# 4_PowerManagement.net
KiCad netlist of a schematic drawn in Altium Designer
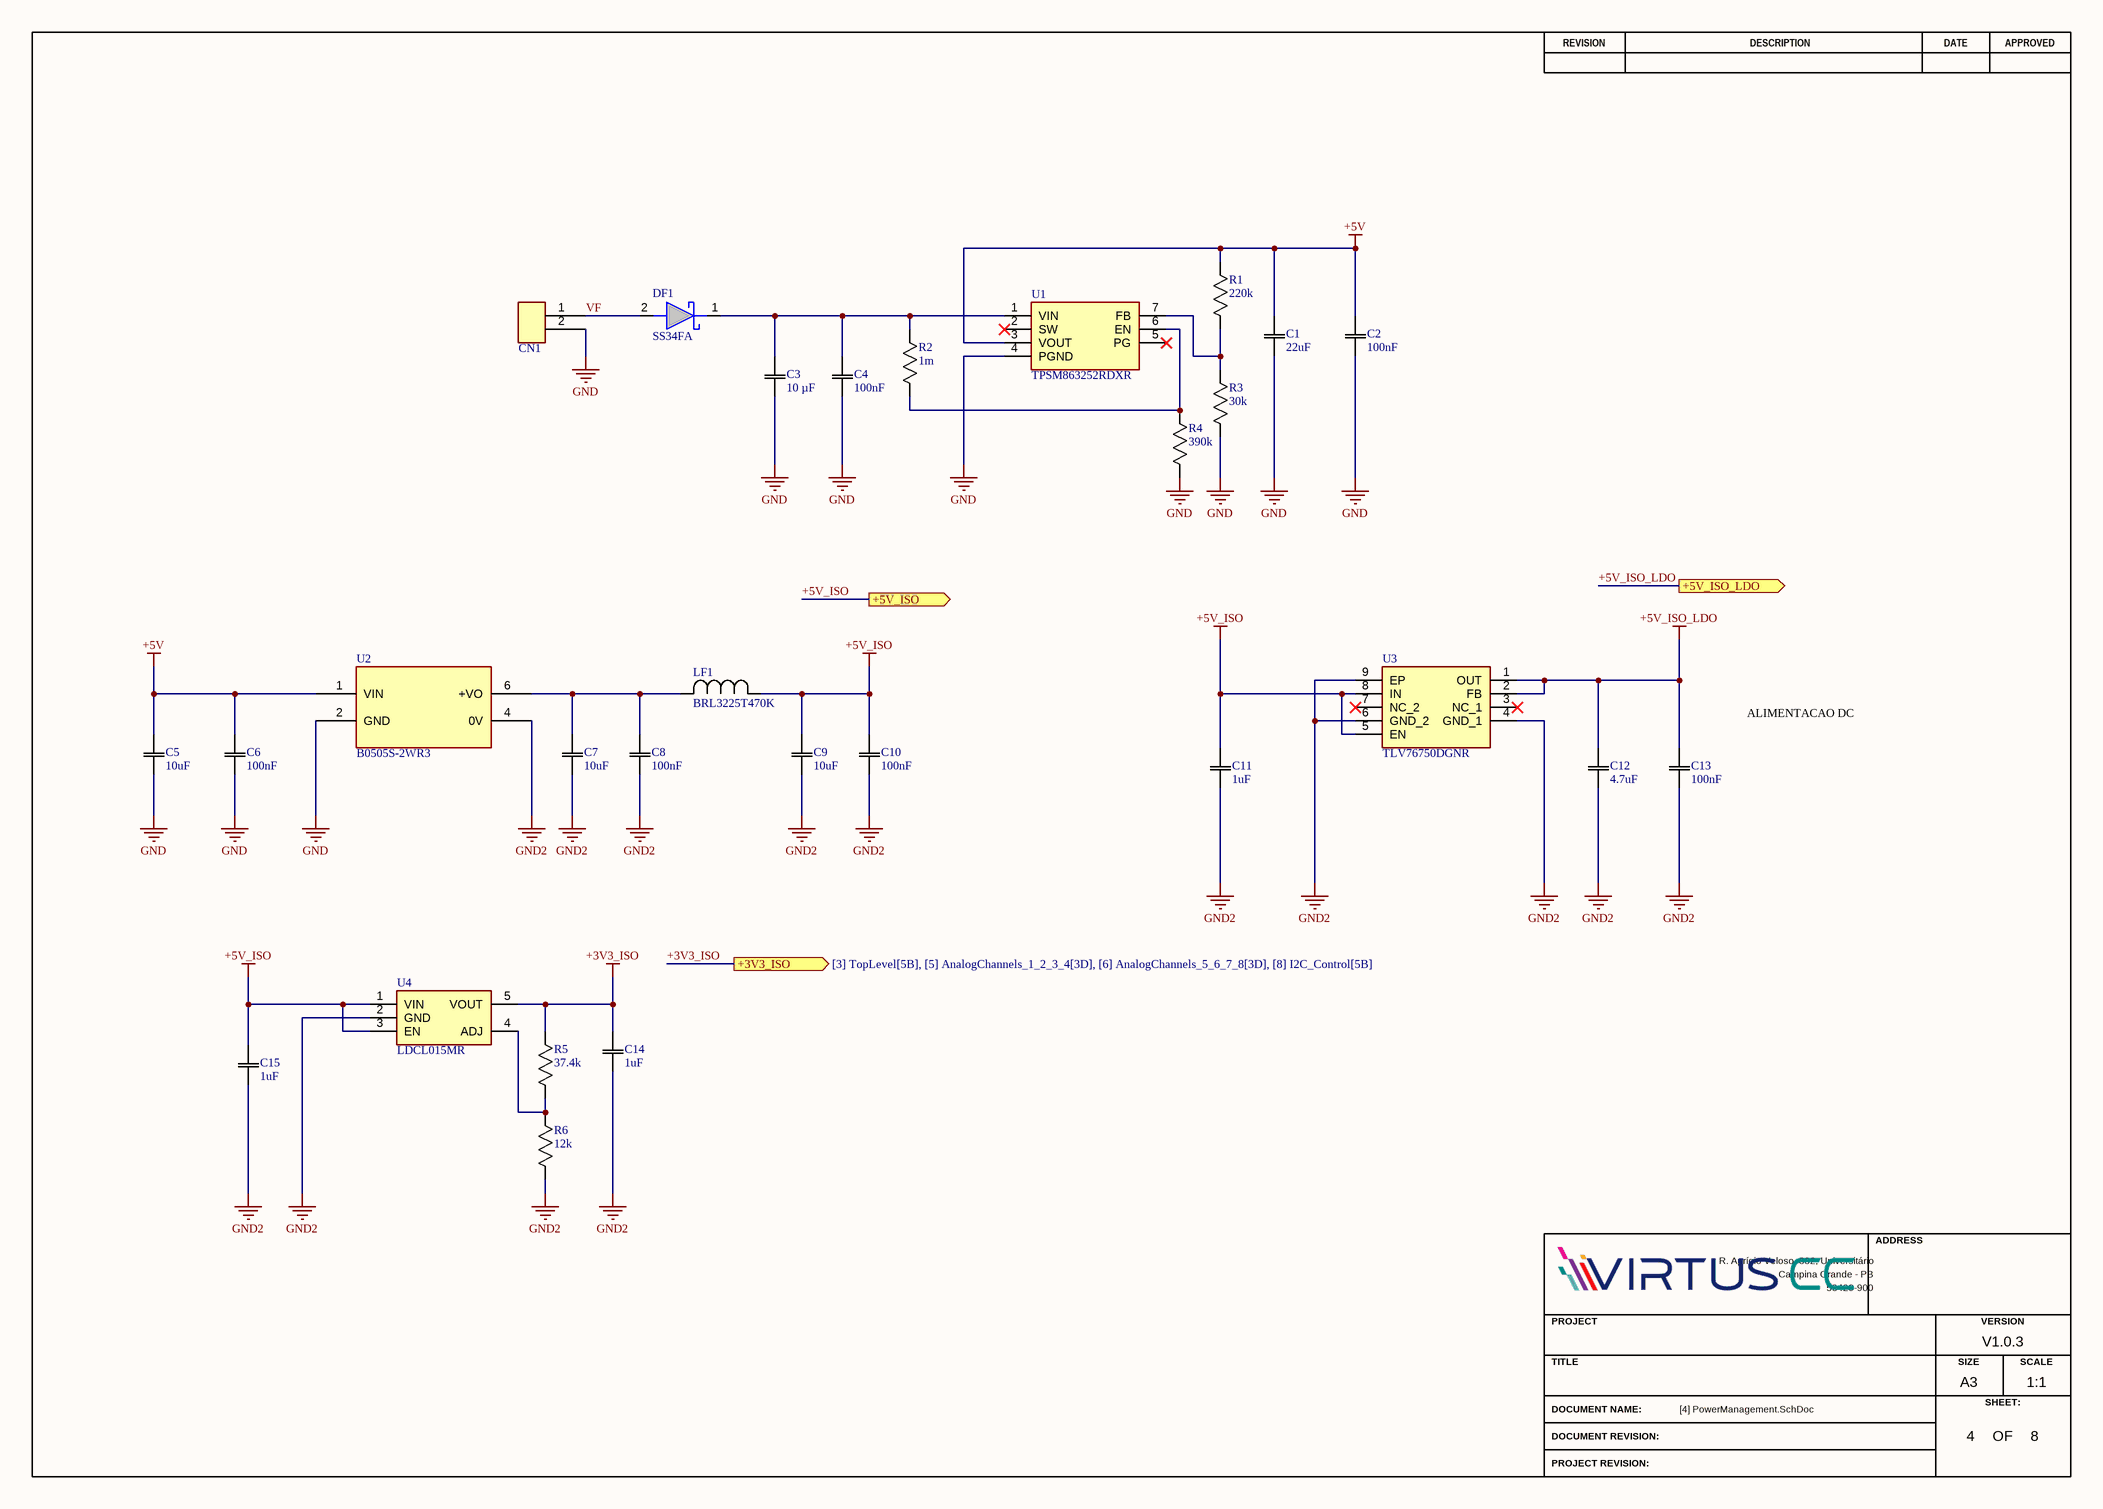
[diagram p0: [4] PowerManagement.SchDoc]

(export (version "E")
  (design (tool "Eeschema 10.0.6"))
  (components
    (comp (ref "C1")
      (value "22uF")
      (footprint "CAPC1608X06N")
      (description "22 µF ±20% 16V Ceramic Capacitor X5R 0603 (1608 Metric)")
      (fields
        (field (name "MANUFACTURER_PART_NUMBER") "CL10A226MO7JZNC")
        (field (name "COPYRIGHT") "Copyright (C) 2026 Ultra Librarian. All rights reserved.")
      )
      (libsource (lib "PCEIOT") (part "CL10A226MO7JZNC"))
    )
    (comp (ref "C2")
      (value "100nF")
      (footprint "CAPC1005X40N")
      (description "0.1 µF ±10% 50V Ceramic Capacitor X7R 0402 (1005 Metric)")
      (fields
        (field (name "MANUFACTURER_PART_NUMBER") "GCM155R71H104KE02D")
        (field (name "COPYRIGHT") "Copyright (C) 2026 Ultra Librarian. All rights reserved.")
      )
      (libsource (lib "PCEIOT") (part "GCM155R71H104KE02D"))
    )
    (comp (ref "C3")
      (value "10 µF")
      (footprint "CAPC1608X06N")
      (description "10 µF ±20% 25V Ceramic Capacitor X5R 0603 (1608 Metric)")
      (fields
        (field (name "MANUFACTURER_PART_NUMBER") "CL10A106MA8NRNC")
        (field (name "COPYRIGHT") "Copyright (C) 2025 Ultra Librarian. All rights reserved.")
      )
      (libsource (lib "PCEIOT") (part "CL10A106MA8NRNC"))
    )
    (comp (ref "C4")
      (value "100nF")
      (footprint "CAPC1005X40N")
      (description "0.1 µF ±10% 50V Ceramic Capacitor X7R 0402 (1005 Metric)")
      (fields
        (field (name "MANUFACTURER_PART_NUMBER") "GCM155R71H104KE02D")
        (field (name "COPYRIGHT") "Copyright (C) 2026 Ultra Librarian. All rights reserved.")
      )
      (libsource (lib "PCEIOT") (part "GCM155R71H104KE02D"))
    )
    (comp (ref "C5")
      (value "10uF")
      (footprint "CAPC1005X40N")
      (description "10 µF ±20% 10V Ceramic Capacitor X5R 0402 (1005 Metric)")
      (fields
        (field (name "MANUFACTURER_PART_NUMBER") "GRT155R61A106ME13D")
        (field (name "COPYRIGHT") "Copyright (C) 2026 Ultra Librarian. All rights reserved.")
      )
      (libsource (lib "PCEIOT") (part "GRT155R61A106ME13D"))
    )
    (comp (ref "C6")
      (value "100nF")
      (footprint "CAPC1005X40N")
      (description "0.1 µF ±10% 50V Ceramic Capacitor X7R 0402 (1005 Metric)")
      (fields
        (field (name "MANUFACTURER_PART_NUMBER") "GCM155R71H104KE02D")
        (field (name "COPYRIGHT") "Copyright (C) 2026 Ultra Librarian. All rights reserved.")
      )
      (libsource (lib "PCEIOT") (part "GCM155R71H104KE02D"))
    )
    (comp (ref "C7")
      (value "10uF")
      (footprint "CAPC1005X40N")
      (description "10 µF ±20% 10V Ceramic Capacitor X5R 0402 (1005 Metric)")
      (fields
        (field (name "MANUFACTURER_PART_NUMBER") "GRT155R61A106ME13D")
        (field (name "COPYRIGHT") "Copyright (C) 2026 Ultra Librarian. All rights reserved.")
      )
      (libsource (lib "PCEIOT") (part "GRT155R61A106ME13D"))
    )
    (comp (ref "C8")
      (value "100nF")
      (footprint "CAPC1005X40N")
      (description "0.1 µF ±10% 50V Ceramic Capacitor X7R 0402 (1005 Metric)")
      (fields
        (field (name "MANUFACTURER_PART_NUMBER") "GCM155R71H104KE02D")
        (field (name "COPYRIGHT") "Copyright (C) 2026 Ultra Librarian. All rights reserved.")
      )
      (libsource (lib "PCEIOT") (part "GCM155R71H104KE02D"))
    )
    (comp (ref "C9")
      (value "10uF")
      (footprint "CAPC1005X40N")
      (description "10 µF ±20% 10V Ceramic Capacitor X5R 0402 (1005 Metric)")
      (fields
        (field (name "MANUFACTURER_PART_NUMBER") "GRT155R61A106ME13D")
        (field (name "COPYRIGHT") "Copyright (C) 2026 Ultra Librarian. All rights reserved.")
      )
      (libsource (lib "PCEIOT") (part "GRT155R61A106ME13D"))
    )
    (comp (ref "C10")
      (value "100nF")
      (footprint "CAPC1005X40N")
      (description "0.1 µF ±10% 50V Ceramic Capacitor X7R 0402 (1005 Metric)")
      (fields
        (field (name "MANUFACTURER_PART_NUMBER") "GCM155R71H104KE02D")
        (field (name "COPYRIGHT") "Copyright (C) 2026 Ultra Librarian. All rights reserved.")
      )
      (libsource (lib "PCEIOT") (part "GCM155R71H104KE02D"))
    )
    (comp (ref "C11")
      (value "1uF")
      (footprint "CAPC1005X40N")
      (description "1 µF ±10% 10V Ceramic Capacitor X7R 0402 (1005 Metric)")
      (fields
        (field (name "MANUFACTURER_PART_NUMBER") "GRM155Z71A105KE01D")
        (field (name "COPYRIGHT") "Copyright (C) 2025 Ultra Librarian. All rights reserved.")
      )
      (libsource (lib "PCEIOT") (part "GRM155Z71A105KE01D"))
    )
    (comp (ref "C12")
      (value "4.7uF")
      (footprint "CAPC1005X40N")
      (description "4.7 µF ±20% 10V Ceramic Capacitor X5R 0402 (1005 Metric)")
      (fields
        (field (name "MANUFACTURER_PART_NUMBER") "GRM155R61A475MEAAD")
        (field (name "COPYRIGHT") "Copyright (C) 2025 Ultra Librarian. All rights reserved.")
      )
      (libsource (lib "PCEIOT") (part "GRM155R61A475MEAAD"))
    )
    (comp (ref "C13")
      (value "100nF")
      (footprint "CAPC1005X40N")
      (description "0.1 µF ±10% 50V Ceramic Capacitor X7R 0402 (1005 Metric)")
      (fields
        (field (name "MANUFACTURER_PART_NUMBER") "GCM155R71H104KE02D")
        (field (name "COPYRIGHT") "Copyright (C) 2026 Ultra Librarian. All rights reserved.")
      )
      (libsource (lib "PCEIOT") (part "GCM155R71H104KE02D"))
    )
    (comp (ref "C14")
      (value "1uF")
      (footprint "CAPC1005X40N")
      (description "1 µF ±10% 10V Ceramic Capacitor X7R 0402 (1005 Metric)")
      (fields
        (field (name "MANUFACTURER_PART_NUMBER") "GRM155Z71A105KE01D")
        (field (name "COPYRIGHT") "Copyright (C) 2025 Ultra Librarian. All rights reserved.")
      )
      (libsource (lib "PCEIOT") (part "GRM155Z71A105KE01D"))
    )
    (comp (ref "C15")
      (value "1uF")
      (footprint "CAPC1005X40N")
      (description "1 µF ±10% 10V Ceramic Capacitor X7R 0402 (1005 Metric)")
      (fields
        (field (name "MANUFACTURER_PART_NUMBER") "GRM155Z71A105KE01D")
        (field (name "COPYRIGHT") "Copyright (C) 2025 Ultra Librarian. All rights reserved.")
      )
      (libsource (lib "PCEIOT") (part "GRM155Z71A105KE01D"))
    )
    (comp (ref "CN1")
      (value "JDCN2.0")
      (footprint "JACK - P4")
      (description "Conector Fonte. JDCN2.0")
      (libsource (lib "PCEIOT") (part "JDCN2.0"))
    )
    (comp (ref "DF1")
      (value "SS34FA")
      (footprint "SODFL3618X143N")
      (fields (field (name "MOUSER PART NUMBER") "512-SS34FA"))
      (libsource (lib "PCEIOT") (part "SS34FA"))
    )
    (comp (ref "LF1")
      (value "BRL3225T470K")
      (footprint "IND_TAIYO_BRL3225_TAY")
      (description "47 µH Semi-Shielded Drum Core, Wirewound Inductor 390 mA 1.2Ohm Max 1210 (3225 Metric)")
      (fields (field (name "COPYRIGHT") "Copyright (C) 2025 Ultra Librarian. All rights reserved."))
      (libsource (lib "PCEIOT") (part "BRL3225T470K"))
    )
    (comp (ref "R1")
      (value "220k")
      (footprint "RESC1005X40N")
      (description "220 kOhms ±1% 0.063W, 1/16W Chip Resistor 0402 (1005 Metric) Moisture Resistant Thick Film")
      (fields
        (field (name "MANUFACTURER_PART_NUMBER") "RC0402FR-07220KL")
        (field (name "COPYRIGHT") "Copyright (C) 2026 Ultra Librarian. All rights reserved.")
      )
      (libsource (lib "PCEIOT") (part "RC0402FR-07220KL"))
    )
    (comp (ref "R2")
      (value "1m")
      (footprint "RESC1005X40N")
      (description "1 MOhms ±1% 0.063W, 1/16W Chip Resistor 0402 (1005 Metric) Moisture Resistant Thick Film")
      (fields
        (field (name "MANUFACTURER_PART_NUMBER") "RC0402FR-071ML")
        (field (name "COPYRIGHT") "Copyright (C) 2026 Ultra Librarian. All rights reserved.")
      )
      (libsource (lib "PCEIOT") (part "RC0402FR-071ML"))
    )
    (comp (ref "R3")
      (value "30k")
      (footprint "RESC1005X40N")
      (description "30 kOhms ±1% 0.063W, 1/16W Chip Resistor 0402 (1005 Metric) Moisture Resistant Thick Film")
      (fields
        (field (name "MANUFACTURER_PART_NUMBER") "RC0402FR-0730KL")
        (field (name "COPYRIGHT") "Copyright (C) 2026 Ultra Librarian. All rights reserved.")
      )
      (libsource (lib "PCEIOT") (part "RC0402FR-0730KL"))
    )
    (comp (ref "R4")
      (value "390k")
      (footprint "RESC1005X40N")
      (description "390 kOhms ±1% 0.063W, 1/16W Chip Resistor 0402 (1005 Metric) Moisture Resistant Thick Film")
      (fields
        (field (name "MANUFACTURER_PART_NUMBER") "RC0402FR-07390KL")
        (field (name "COPYRIGHT") "Copyright (C) 2026 Ultra Librarian. All rights reserved.")
      )
      (libsource (lib "PCEIOT") (part "RC0402FR-07390KL"))
    )
    (comp (ref "R5")
      (value "37.4k")
      (footprint "RESC1005X40N")
      (description "37.4 kOhms ±1% 0.063W, 1/16W Chip Resistor 0402 (1005 Metric) Moisture Resistant Thick Film")
      (fields
        (field (name "MANUFACTURER_PART_NUMBER") "RC0402FR-0737K4L")
        (field (name "COPYRIGHT") "Copyright (C) 2026 Ultra Librarian. All rights reserved.")
      )
      (libsource (lib "PCEIOT") (part "RC0402FR-0737K4L"))
    )
    (comp (ref "R6")
      (value "12k")
      (footprint "RESC1005X40N")
      (description "12 kOhms ±1% 0.063W, 1/16W Chip Resistor 0402 (1005 Metric) Moisture Resistant Thick Film")
      (fields
        (field (name "MANUFACTURER_PART_NUMBER") "RC0402FR-0712KL")
        (field (name "COPYRIGHT") "Copyright (C) 2025 Ultra Librarian. All rights reserved.")
      )
      (libsource (lib "PCEIOT") (part "RC0402FR-0712KL"))
    )
    (comp (ref "U1")
      (value "TPSM863252RDXR")
      (footprint "RDX0007A-MFG - 2")
      (description "3-V to 17-V input voltage, 3-A Eco-mode synchronous buck module 7-QFN-FCMOD -40 to 125")
      (fields (field (name "COPYRIGHT") "Copyright (C) 2025 Ultra Librarian. All rights reserved."))
      (libsource (lib "PCEIOT") (part "TPSM863252RDXR"))
    )
    (comp (ref "U2")
      (value "B0505S-2WR3")
      (footprint "B_S-2WR2_MNS")
      (description "Isolated Module DC DC Converter 1 Output 5V 400mA 4.5V - 5.5V Input")
      (fields (field (name "COPYRIGHT") "Copyright (C) 2026 Ultra Librarian. All rights reserved."))
      (libsource (lib "PCEIOT") (part "B0505S-2WR3"))
    )
    (comp (ref "U3")
      (value "TLV76750DGNR")
      (footprint "VSSOP_0DGNR_TEX")
      (fields (field (name "MOUSER PART NUMBER") "595-TLV76750DGNR"))
      (libsource (lib "PCEIOT") (part "TLV76750DGNR"))
    )
    (comp (ref "U4")
      (value "LDCL015MR")
      (footprint "SOT95P280X145-5N")
      (description "Linear Voltage Regulator IC Positive Adjustable 1 Output 150mA SOT-23-5")
      (fields (field (name "MOUSER PART NUMBER") "511-LDCL015MR"))
      (libsource (lib "PCEIOT") (part "LDCL015MR"))
    )
  )
  (nets
    (net (code "1") (name "+3V3_ISO") (class "Default")
      (node (ref "C14") (pin "2") (pinfunction "2_2") (pintype "passive"))
      (node (ref "R5") (pin "1") (pinfunction "1_1") (pintype "passive"))
      (node (ref "U4") (pin "5") (pinfunction "VOUT_5") (pintype "passive"))
    )
    (net (code "2") (name "+5V") (class "Default")
      (node (ref "C1") (pin "2") (pinfunction "2_2") (pintype "passive"))
      (node (ref "C2") (pin "2") (pinfunction "2_2") (pintype "passive"))
      (node (ref "C5") (pin "2") (pinfunction "2_2") (pintype "passive"))
      (node (ref "C6") (pin "2") (pinfunction "2_2") (pintype "passive"))
      (node (ref "R1") (pin "1") (pinfunction "1_1") (pintype "passive"))
      (node (ref "U1") (pin "3") (pinfunction "VOUT_3") (pintype "power_in"))
      (node (ref "U2") (pin "1") (pinfunction "VIN_1") (pintype "power_in"))
    )
    (net (code "3") (name "+5V_ISO") (class "Default")
      (node (ref "C10") (pin "2") (pinfunction "2_2") (pintype "passive"))
      (node (ref "C11") (pin "2") (pinfunction "2_2") (pintype "passive"))
      (node (ref "C15") (pin "2") (pinfunction "2_2") (pintype "passive"))
      (node (ref "C9") (pin "2") (pinfunction "2_2") (pintype "passive"))
      (node (ref "LF1") (pin "1") (pinfunction "1_1") (pintype "passive"))
      (node (ref "U3") (pin "5") (pinfunction "EN_5") (pintype "passive"))
      (node (ref "U3") (pin "8") (pinfunction "IN_8") (pintype "passive"))
      (node (ref "U4") (pin "1") (pinfunction "VIN_1") (pintype "passive"))
      (node (ref "U4") (pin "3") (pinfunction "EN_3") (pintype "passive"))
    )
    (net (code "4") (name "+5V_ISO_LDO") (class "Default")
      (node (ref "C12") (pin "2") (pinfunction "2_2") (pintype "passive"))
      (node (ref "C13") (pin "2") (pinfunction "2_2") (pintype "passive"))
      (node (ref "U3") (pin "1") (pinfunction "OUT_1") (pintype "passive"))
      (node (ref "U3") (pin "2") (pinfunction "FB_2") (pintype "passive"))
    )
    (net (code "5") (name "/VF") (class "Default")
      (node (ref "CN1") (pin "1") (pinfunction "1_1") (pintype "passive"))
      (node (ref "DF1") (pin "2") (pinfunction "A_2") (pintype "passive"))
    )
    (net (code "6") (name "GND") (class "Default")
      (node (ref "C1") (pin "1") (pinfunction "1_1") (pintype "passive"))
      (node (ref "C2") (pin "1") (pinfunction "1_1") (pintype "passive"))
      (node (ref "C3") (pin "1") (pinfunction "1_1") (pintype "passive"))
      (node (ref "C4") (pin "1") (pinfunction "1_1") (pintype "passive"))
      (node (ref "C5") (pin "1") (pinfunction "1_1") (pintype "passive"))
      (node (ref "C6") (pin "1") (pinfunction "1_1") (pintype "passive"))
      (node (ref "CN1") (pin "2") (pinfunction "2_2") (pintype "passive"))
      (node (ref "R3") (pin "2") (pinfunction "2_2") (pintype "passive"))
      (node (ref "R4") (pin "2") (pinfunction "2_2") (pintype "passive"))
      (node (ref "U1") (pin "4") (pinfunction "PGND_4") (pintype "power_in"))
      (node (ref "U2") (pin "2") (pinfunction "GND_2") (pintype "power_in"))
    )
    (net (code "7") (name "GND2") (class "Default")
      (node (ref "C10") (pin "1") (pinfunction "1_1") (pintype "passive"))
      (node (ref "C11") (pin "1") (pinfunction "1_1") (pintype "passive"))
      (node (ref "C12") (pin "1") (pinfunction "1_1") (pintype "passive"))
      (node (ref "C13") (pin "1") (pinfunction "1_1") (pintype "passive"))
      (node (ref "C14") (pin "1") (pinfunction "1_1") (pintype "passive"))
      (node (ref "C15") (pin "1") (pinfunction "1_1") (pintype "passive"))
      (node (ref "C7") (pin "1") (pinfunction "1_1") (pintype "passive"))
      (node (ref "C8") (pin "1") (pinfunction "1_1") (pintype "passive"))
      (node (ref "C9") (pin "1") (pinfunction "1_1") (pintype "passive"))
      (node (ref "R6") (pin "2") (pinfunction "2_2") (pintype "passive"))
      (node (ref "U2") (pin "4") (pinfunction "0V_4") (pintype "passive"))
      (node (ref "U3") (pin "4") (pinfunction "GND_1_4") (pintype "passive"))
      (node (ref "U3") (pin "6") (pinfunction "GND_2_6") (pintype "passive"))
      (node (ref "U3") (pin "9") (pinfunction "EP_9") (pintype "passive"))
      (node (ref "U4") (pin "2") (pinfunction "GND_2") (pintype "power_in"))
    )
    (net (code "8") (name "Net-(DF1-K)") (class "Default")
      (node (ref "C3") (pin "2") (pinfunction "2_2") (pintype "passive"))
      (node (ref "C4") (pin "2") (pinfunction "2_2") (pintype "passive"))
      (node (ref "DF1") (pin "1") (pinfunction "K_1") (pintype "passive"))
      (node (ref "R2") (pin "1") (pinfunction "1_1") (pintype "passive"))
      (node (ref "U1") (pin "1") (pinfunction "VIN_1") (pintype "power_in"))
    )
    (net (code "9") (name "Net-(U1-EN)") (class "Default")
      (node (ref "R2") (pin "2") (pinfunction "2_2") (pintype "passive"))
      (node (ref "R4") (pin "1") (pinfunction "1_1") (pintype "passive"))
      (node (ref "U1") (pin "6") (pinfunction "EN_6") (pintype "passive"))
    )
    (net (code "10") (name "Net-(U1-FB)") (class "Default")
      (node (ref "R1") (pin "2") (pinfunction "2_2") (pintype "passive"))
      (node (ref "R3") (pin "1") (pinfunction "1_1") (pintype "passive"))
      (node (ref "U1") (pin "7") (pinfunction "FB_7") (pintype "passive"))
    )
    (net (code "11") (name "Net-(U2-+VO)") (class "Default")
      (node (ref "C7") (pin "2") (pinfunction "2_2") (pintype "passive"))
      (node (ref "C8") (pin "2") (pinfunction "2_2") (pintype "passive"))
      (node (ref "LF1") (pin "2") (pinfunction "2_2") (pintype "passive"))
      (node (ref "U2") (pin "6") (pinfunction "+VO_6") (pintype "power_in"))
    )
    (net (code "12") (name "Net-(U4-ADJ)") (class "Default")
      (node (ref "R5") (pin "2") (pinfunction "2_2") (pintype "passive"))
      (node (ref "R6") (pin "1") (pinfunction "1_1") (pintype "passive"))
      (node (ref "U4") (pin "4") (pinfunction "ADJ_4") (pintype "passive"))
    )
    (net (code "13") (name "unconnected-(U1-PG-Pad5)") (class "Default")
      (node (ref "U1") (pin "5") (pinfunction "PG_5") (pintype "open_collector+no_connect"))
    )
    (net (code "14") (name "unconnected-(U1-SW-Pad2)") (class "Default")
      (node (ref "U1") (pin "2") (pinfunction "SW_2") (pintype "passive+no_connect"))
    )
    (net (code "15") (name "unconnected-(U3-NC_1-Pad3)") (class "Default")
      (node (ref "U3") (pin "3") (pinfunction "NC_1_3") (pintype "passive+no_connect"))
    )
    (net (code "16") (name "unconnected-(U3-NC_2-Pad7)") (class "Default")
      (node (ref "U3") (pin "7") (pinfunction "NC_2_7") (pintype "passive+no_connect"))
    )
  )
)
